# Blocky_Uno_v2.net
KiCad netlist of a schematic drawn in EAGLE
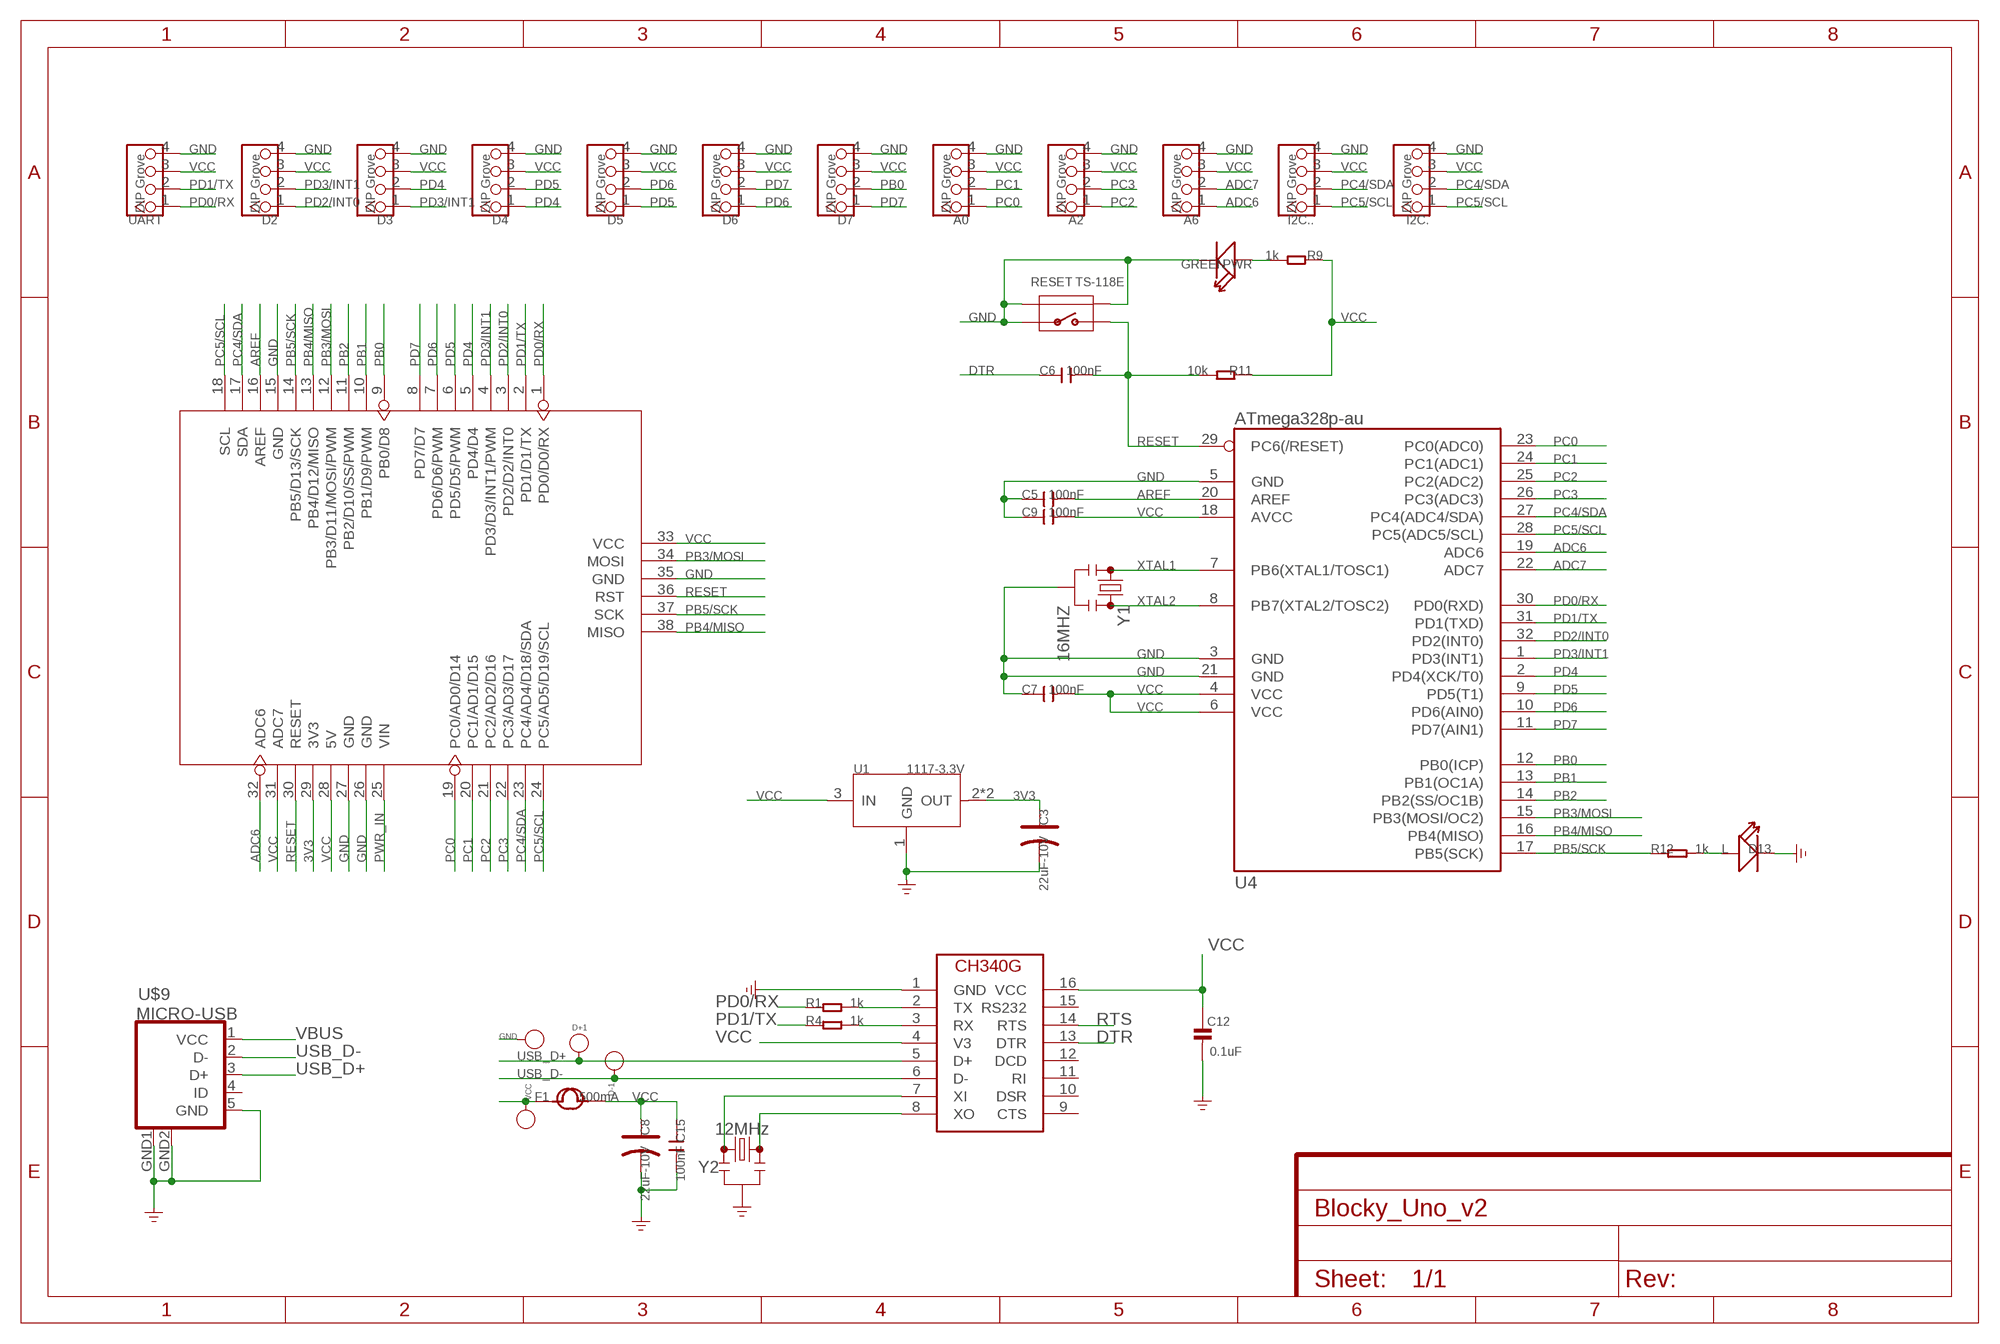
[diagram p0: schematic, sheet 1]

(export (version "E")
  (design (tool "Eeschema 10.0.6"))
  (components
    (comp (ref "A0")
      (value "DIP Grove")
      (footprint "eagle-import:4P-2.0")
      (libsource (lib "eagle-import") (part "Connector _TWIG-4P-2.0-2.0"))
    )
    (comp (ref "A2")
      (value "DIP Grove")
      (footprint "eagle-import:4P-2.0")
      (libsource (lib "eagle-import") (part "Connector _TWIG-4P-2.0-2.0"))
    )
    (comp (ref "A6")
      (value "DIP Grove")
      (footprint "eagle-import:4P-2.0")
      (libsource (lib "eagle-import") (part "Connector _TWIG-4P-2.0-2.0"))
    )
    (comp (ref "C3")
      (value "22uF-10V")
      (footprint "eagle-import:AVX-A")
      (libsource (lib "eagle-import") (part "CAP-AVX-A"))
    )
    (comp (ref "C5")
      (value "100nF")
      (footprint "eagle-import:C0603")
      (libsource (lib "eagle-import") (part "C-0603"))
    )
    (comp (ref "C6")
      (value "100nF")
      (footprint "eagle-import:C0603")
      (libsource (lib "eagle-import") (part "C-0603"))
    )
    (comp (ref "C7")
      (value "100nF")
      (footprint "eagle-import:C0603")
      (libsource (lib "eagle-import") (part "C-0603"))
    )
    (comp (ref "C8")
      (value "22uF-10V")
      (footprint "eagle-import:AVX-A")
      (libsource (lib "eagle-import") (part "CAP-AVX-A"))
    )
    (comp (ref "C9")
      (value "100nF")
      (footprint "eagle-import:C0603")
      (libsource (lib "eagle-import") (part "C-0603"))
    )
    (comp (ref "C12")
      (value "0.1uF")
      (footprint "eagle-import:_0603")
      (libsource (lib "eagle-import") (part "CAP_CERAMIC_0603"))
    )
    (comp (ref "C15")
      (value "100nF")
      (footprint "eagle-import:C0603")
      (libsource (lib "eagle-import") (part "C-0603"))
    )
    (comp (ref "D+1")
      (value "PAD-TEST-POINT'4545'")
      (footprint "eagle-import:TP_4545")
      (fields (field (name "PARTNO") "DNP"))
      (libsource (lib "eagle-import") (part "PAD-TEST-POINT'4545'"))
    )
    (comp (ref "D-1")
      (value "PAD-TEST-POINT'4545'")
      (footprint "eagle-import:TP_4545")
      (fields (field (name "PARTNO") "DNP"))
      (libsource (lib "eagle-import") (part "PAD-TEST-POINT'4545'"))
    )
    (comp (ref "D2")
      (value "DIP Grove")
      (footprint "eagle-import:4P-2.0")
      (libsource (lib "eagle-import") (part "TWIG-4P-2.0-2.0"))
    )
    (comp (ref "D3")
      (value "DIP Grove")
      (footprint "eagle-import:4P-2.0")
      (libsource (lib "eagle-import") (part "TWIG-4P-2.0-2.0"))
    )
    (comp (ref "D4")
      (value "DIP Grove")
      (footprint "eagle-import:4P-2.0")
      (libsource (lib "eagle-import") (part "TWIG-4P-2.0-2.0"))
    )
    (comp (ref "D5")
      (value "DIP Grove")
      (footprint "eagle-import:4P-2.0")
      (libsource (lib "eagle-import") (part "TWIG-4P-2.0-2.0"))
    )
    (comp (ref "D6")
      (value "DIP Grove")
      (footprint "eagle-import:4P-2.0")
      (libsource (lib "eagle-import") (part "TWIG-4P-2.0-2.0"))
    )
    (comp (ref "D7")
      (value "DIP Grove")
      (footprint "eagle-import:4P-2.0")
      (libsource (lib "eagle-import") (part "TWIG-4P-2.0-2.0"))
    )
    (comp (ref "F1")
      (value "500mA")
      (footprint "eagle-import:F1206")
      (libsource (lib "eagle-import") (part "FUSE'1206'"))
    )
    (comp (ref "GND")
      (value "PAD-TEST-POINT'4545'")
      (footprint "eagle-import:TP_4545")
      (fields (field (name "PARTNO") "DNP"))
      (libsource (lib "eagle-import") (part "PAD-TEST-POINT'4545'"))
    )
    (comp (ref "I2C.")
      (value "DIP Grove")
      (footprint "eagle-import:4P-2.0")
      (libsource (lib "eagle-import") (part "TWIG-4P-2.0-2.0"))
    )
    (comp (ref "I2C..")
      (value "DIP Grove")
      (footprint "eagle-import:4P-2.0")
      (libsource (lib "eagle-import") (part "TWIG-4P-2.0-2.0"))
    )
    (comp (ref "L")
      (value "D13")
      (footprint "eagle-import:LED-0603")
      (libsource (lib "eagle-import") (part "LED'0603'"))
    )
    (comp (ref "PWR")
      (value "GREEN")
      (footprint "eagle-import:LED-0603")
      (libsource (lib "eagle-import") (part "LED'0603'"))
    )
    (comp (ref "R1")
      (value "1k")
      (footprint "eagle-import:R0603")
      (libsource (lib "eagle-import") (part "R-0603"))
    )
    (comp (ref "R4")
      (value "1k")
      (footprint "eagle-import:R0603")
      (libsource (lib "eagle-import") (part "R-0603"))
    )
    (comp (ref "R9")
      (value "1k")
      (footprint "eagle-import:R0603")
      (libsource (lib "eagle-import") (part "R-0603"))
    )
    (comp (ref "R11")
      (value "10k")
      (footprint "eagle-import:R0603")
      (libsource (lib "eagle-import") (part "R-0603"))
    )
    (comp (ref "R12")
      (value "1k")
      (footprint "eagle-import:R0603")
      (libsource (lib "eagle-import") (part "R-0603"))
    )
    (comp (ref "RESET")
      (value "TS-118E")
      (footprint "eagle-import:4P-SMD-7X3.5X3.5H")
      (libsource (lib "eagle-import") (part "BUTTON-4P-REINFORCE'TS-1188E'"))
    )
    (comp (ref "U$9")
      (value "MICRO-USB")
      (footprint "eagle-import:MICRO-USB")
      (libsource (lib "eagle-import") (part "MICRO-USB"))
    )
    (comp (ref "U$44")
      (value "CH340G")
      (footprint "eagle-import:SOIC16")
      (libsource (lib "eagle-import") (part "CH340G"))
    )
    (comp (ref "U1")
      (value "1117-3.3V")
      (footprint "eagle-import:SOT89")
      (libsource (lib "eagle-import") (part "LD1117'SOT89'"))
    )
    (comp (ref "U3")
      (value "ARDUINO-38P")
      (footprint "eagle-import:ARDUINO-38P")
      (libsource (lib "eagle-import") (part "ARDUINO-38P"))
    )
    (comp (ref "U4")
      (value "ATmega328p-au")
      (footprint "eagle-import:TQFP32")
      (libsource (lib "eagle-import") (part "ATMEGA8/168/328"))
    )
    (comp (ref "UART")
      (value "DIP Grove")
      (footprint "eagle-import:4P-2.0")
      (libsource (lib "eagle-import") (part "TWIG-4P-2.0-2.0"))
    )
    (comp (ref "VCC")
      (value "PAD-TEST-POINT'4545'")
      (footprint "eagle-import:TP_4545")
      (fields (field (name "PARTNO") "DNP"))
      (libsource (lib "eagle-import") (part "PAD-TEST-POINT'4545'"))
    )
    (comp (ref "Y1")
      (value "16MHZ")
      (footprint "eagle-import:RESONATOR-SMD")
      (libsource (lib "eagle-import") (part "RESONATOR16MHZ"))
    )
    (comp (ref "Y2")
      (value "12MHz")
      (footprint "eagle-import:RESONATOR-SMD-3.2X1.3")
      (libsource (lib "eagle-import") (part "RESONATOR-16MHZSMD_3.2X1.3"))
    )
  )
  (nets
    (net (code "1") (name "/3V3") (class "Default")
      (node (ref "C3") (pin "+") (pinfunction "+_+") (pintype "passive"))
      (node (ref "U1") (pin "2") (pinfunction "OUT_2") (pintype "bidirectional"))
      (node (ref "U1") (pin "4") (pinfunction "OUT_4") (pintype "bidirectional"))
      (node (ref "U3") (pin "29") (pinfunction "3V3_29") (pintype "bidirectional"))
    )
    (net (code "2") (name "/ADC6") (class "Default")
      (node (ref "A6") (pin "1") (pinfunction "1_1") (pintype "bidirectional"))
      (node (ref "U3") (pin "32") (pinfunction "ADC6_32") (pintype "bidirectional"))
      (node (ref "U4") (pin "19") (pinfunction "ADC6_19") (pintype "bidirectional"))
    )
    (net (code "3") (name "/ADC7") (class "Default")
      (node (ref "A6") (pin "2") (pinfunction "2_2") (pintype "bidirectional"))
      (node (ref "U4") (pin "22") (pinfunction "ADC7_22") (pintype "bidirectional"))
    )
    (net (code "4") (name "/AREF") (class "Default")
      (node (ref "C5") (pin "2") (pinfunction "2_2") (pintype "passive"))
      (node (ref "U3") (pin "16") (pinfunction "AREF_16") (pintype "bidirectional"))
      (node (ref "U4") (pin "20") (pinfunction "AREF_20") (pintype "bidirectional"))
    )
    (net (code "5") (name "/DTR") (class "Default")
      (node (ref "C6") (pin "1") (pinfunction "1_1") (pintype "passive"))
      (node (ref "U$44") (pin "13") (pinfunction "DTR_13") (pintype "bidirectional"))
    )
    (net (code "6") (name "/PB0") (class "Default")
      (node (ref "D7") (pin "2") (pinfunction "2_2") (pintype "bidirectional"))
      (node (ref "U3") (pin "9") (pinfunction "PB0/D8_9") (pintype "bidirectional"))
      (node (ref "U4") (pin "12") (pinfunction "PB0(ICP)_12") (pintype "bidirectional"))
    )
    (net (code "7") (name "/PB1") (class "Default")
      (node (ref "U3") (pin "10") (pinfunction "PB1/D9/PWM_10") (pintype "bidirectional"))
      (node (ref "U4") (pin "13") (pinfunction "PB1(OC1A)_13") (pintype "bidirectional"))
    )
    (net (code "8") (name "/PB2") (class "Default")
      (node (ref "U3") (pin "11") (pinfunction "PB2/D10/SS/PWM_11") (pintype "bidirectional"))
      (node (ref "U4") (pin "14") (pinfunction "PB2(SS/OC1B)_14") (pintype "bidirectional"))
    )
    (net (code "9") (name "/PB3{slash}MOSI") (class "Default")
      (node (ref "U3") (pin "12") (pinfunction "PB3/D11/MOSI/PWM_12") (pintype "bidirectional"))
      (node (ref "U3") (pin "34") (pinfunction "MOSI_34") (pintype "bidirectional"))
      (node (ref "U4") (pin "15") (pinfunction "PB3(MOSI/OC2)_15") (pintype "bidirectional"))
    )
    (net (code "10") (name "/PB4{slash}MISO") (class "Default")
      (node (ref "U3") (pin "13") (pinfunction "PB4/D12/MISO_13") (pintype "bidirectional"))
      (node (ref "U3") (pin "38") (pinfunction "MISO_38") (pintype "bidirectional"))
      (node (ref "U4") (pin "16") (pinfunction "PB4(MISO)_16") (pintype "bidirectional"))
    )
    (net (code "11") (name "/PB5{slash}SCK") (class "Default")
      (node (ref "R12") (pin "1") (pinfunction "1_1") (pintype "passive"))
      (node (ref "U3") (pin "14") (pinfunction "PB5/D13/SCK_14") (pintype "bidirectional"))
      (node (ref "U3") (pin "37") (pinfunction "SCK_37") (pintype "bidirectional"))
      (node (ref "U4") (pin "17") (pinfunction "PB5(SCK)_17") (pintype "bidirectional"))
    )
    (net (code "12") (name "/PC0") (class "Default")
      (node (ref "A0") (pin "1") (pinfunction "1_1") (pintype "bidirectional"))
      (node (ref "U3") (pin "19") (pinfunction "PC0/AD0/D14_19") (pintype "bidirectional"))
      (node (ref "U4") (pin "23") (pinfunction "PC0(ADC0)_23") (pintype "bidirectional"))
    )
    (net (code "13") (name "/PC1") (class "Default")
      (node (ref "A0") (pin "2") (pinfunction "2_2") (pintype "bidirectional"))
      (node (ref "U3") (pin "20") (pinfunction "PC1/AD1/D15_20") (pintype "bidirectional"))
      (node (ref "U4") (pin "24") (pinfunction "PC1(ADC1)_24") (pintype "bidirectional"))
    )
    (net (code "14") (name "/PC2") (class "Default")
      (node (ref "A2") (pin "1") (pinfunction "1_1") (pintype "bidirectional"))
      (node (ref "U3") (pin "21") (pinfunction "PC2/AD2/D16_21") (pintype "bidirectional"))
      (node (ref "U4") (pin "25") (pinfunction "PC2(ADC2)_25") (pintype "bidirectional"))
    )
    (net (code "15") (name "/PC3") (class "Default")
      (node (ref "A2") (pin "2") (pinfunction "2_2") (pintype "bidirectional"))
      (node (ref "U3") (pin "22") (pinfunction "PC3/AD3/D17_22") (pintype "bidirectional"))
      (node (ref "U4") (pin "26") (pinfunction "PC3(ADC3)_26") (pintype "bidirectional"))
    )
    (net (code "16") (name "/PC4{slash}SDA") (class "Default")
      (node (ref "I2C.") (pin "2") (pinfunction "2_2") (pintype "bidirectional"))
      (node (ref "I2C..") (pin "2") (pinfunction "2_2") (pintype "bidirectional"))
      (node (ref "U3") (pin "17") (pinfunction "SDA_17") (pintype "bidirectional"))
      (node (ref "U3") (pin "23") (pinfunction "PC4/AD4/D18/SDA_23") (pintype "bidirectional"))
      (node (ref "U4") (pin "27") (pinfunction "PC4(ADC4/SDA)_27") (pintype "bidirectional"))
    )
    (net (code "17") (name "/PC5{slash}SCL") (class "Default")
      (node (ref "I2C.") (pin "1") (pinfunction "1_1") (pintype "bidirectional"))
      (node (ref "I2C..") (pin "1") (pinfunction "1_1") (pintype "bidirectional"))
      (node (ref "U3") (pin "18") (pinfunction "SCL_18") (pintype "bidirectional"))
      (node (ref "U3") (pin "24") (pinfunction "PC5/AD5/D19/SCL_24") (pintype "bidirectional"))
      (node (ref "U4") (pin "28") (pinfunction "PC5(ADC5/SCL)_28") (pintype "bidirectional"))
    )
    (net (code "18") (name "/PD0{slash}RX") (class "Default")
      (node (ref "R1") (pin "1") (pinfunction "1_1") (pintype "passive"))
      (node (ref "U3") (pin "1") (pinfunction "PD0/D0/RX_1") (pintype "bidirectional"))
      (node (ref "U4") (pin "30") (pinfunction "PD0(RXD)_30") (pintype "bidirectional"))
      (node (ref "UART") (pin "1") (pinfunction "1_1") (pintype "bidirectional"))
    )
    (net (code "19") (name "/PD1{slash}TX") (class "Default")
      (node (ref "R4") (pin "1") (pinfunction "1_1") (pintype "passive"))
      (node (ref "U3") (pin "2") (pinfunction "PD1/D1/TX_2") (pintype "bidirectional"))
      (node (ref "U4") (pin "31") (pinfunction "PD1(TXD)_31") (pintype "bidirectional"))
      (node (ref "UART") (pin "2") (pinfunction "2_2") (pintype "bidirectional"))
    )
    (net (code "20") (name "/PD2{slash}INT0") (class "Default")
      (node (ref "D2") (pin "1") (pinfunction "1_1") (pintype "bidirectional"))
      (node (ref "U3") (pin "3") (pinfunction "PD2/D2/INT0_3") (pintype "bidirectional"))
      (node (ref "U4") (pin "32") (pinfunction "PD2(INT0)_32") (pintype "bidirectional"))
    )
    (net (code "21") (name "/PD3{slash}INT1") (class "Default")
      (node (ref "D2") (pin "2") (pinfunction "2_2") (pintype "bidirectional"))
      (node (ref "D3") (pin "1") (pinfunction "1_1") (pintype "bidirectional"))
      (node (ref "U3") (pin "4") (pinfunction "PD3/D3/INT1/PWM_4") (pintype "bidirectional"))
      (node (ref "U4") (pin "1") (pinfunction "PD3(INT1)_1") (pintype "bidirectional"))
    )
    (net (code "22") (name "/PD4") (class "Default")
      (node (ref "D3") (pin "2") (pinfunction "2_2") (pintype "bidirectional"))
      (node (ref "D4") (pin "1") (pinfunction "1_1") (pintype "bidirectional"))
      (node (ref "U3") (pin "5") (pinfunction "PD4/D4_5") (pintype "bidirectional"))
      (node (ref "U4") (pin "2") (pinfunction "PD4(XCK/T0)_2") (pintype "bidirectional"))
    )
    (net (code "23") (name "/PD5") (class "Default")
      (node (ref "D4") (pin "2") (pinfunction "2_2") (pintype "bidirectional"))
      (node (ref "D5") (pin "1") (pinfunction "1_1") (pintype "bidirectional"))
      (node (ref "U3") (pin "6") (pinfunction "PD5/D5/PWM_6") (pintype "bidirectional"))
      (node (ref "U4") (pin "9") (pinfunction "PD5(T1)_9") (pintype "bidirectional"))
    )
    (net (code "24") (name "/PD6") (class "Default")
      (node (ref "D5") (pin "2") (pinfunction "2_2") (pintype "bidirectional"))
      (node (ref "D6") (pin "1") (pinfunction "1_1") (pintype "bidirectional"))
      (node (ref "U3") (pin "7") (pinfunction "PD6/D6/PWM_7") (pintype "bidirectional"))
      (node (ref "U4") (pin "10") (pinfunction "PD6(AIN0)_10") (pintype "bidirectional"))
    )
    (net (code "25") (name "/PD7") (class "Default")
      (node (ref "D6") (pin "2") (pinfunction "2_2") (pintype "bidirectional"))
      (node (ref "D7") (pin "1") (pinfunction "1_1") (pintype "bidirectional"))
      (node (ref "U3") (pin "8") (pinfunction "PD7/D7_8") (pintype "bidirectional"))
      (node (ref "U4") (pin "11") (pinfunction "PD7(AIN1)_11") (pintype "bidirectional"))
    )
    (net (code "26") (name "/PWR_IN") (class "Default")
      (node (ref "U3") (pin "25") (pinfunction "VIN_25") (pintype "bidirectional"))
    )
    (net (code "27") (name "/RESET") (class "Default")
      (node (ref "C6") (pin "2") (pinfunction "2_2") (pintype "passive"))
      (node (ref "R11") (pin "2") (pinfunction "2_2") (pintype "passive"))
      (node (ref "RESET") (pin "2") (pinfunction "2_2") (pintype "bidirectional"))
      (node (ref "U3") (pin "30") (pinfunction "RESET_30") (pintype "bidirectional"))
      (node (ref "U3") (pin "36") (pinfunction "RST_36") (pintype "bidirectional"))
      (node (ref "U4") (pin "29") (pinfunction "PC6(/RESET)_29") (pintype "bidirectional"))
    )
    (net (code "28") (name "/RTS") (class "Default")
      (node (ref "U$44") (pin "14") (pinfunction "RTS_14") (pintype "bidirectional"))
    )
    (net (code "29") (name "/USB_D+") (class "Default")
      (node (ref "D+1") (pin "T") (pinfunction "T_T") (pintype "bidirectional"))
      (node (ref "U$44") (pin "5") (pinfunction "D+_5") (pintype "bidirectional"))
      (node (ref "U$9") (pin "3") (pinfunction "D+_3") (pintype "bidirectional"))
    )
    (net (code "30") (name "/USB_D-") (class "Default")
      (node (ref "D-1") (pin "T") (pinfunction "T_T") (pintype "bidirectional"))
      (node (ref "U$44") (pin "6") (pinfunction "D-_6") (pintype "bidirectional"))
      (node (ref "U$9") (pin "2") (pinfunction "D-_2") (pintype "bidirectional"))
    )
    (net (code "31") (name "/VBUS") (class "Default")
      (node (ref "F1") (pin "1") (pinfunction "1_1") (pintype "bidirectional"))
      (node (ref "U$9") (pin "1") (pinfunction "VCC_1") (pintype "power_in"))
      (node (ref "VCC") (pin "T") (pinfunction "T_T") (pintype "bidirectional"))
    )
    (net (code "32") (name "/VCC") (class "Default")
      (node (ref "A0") (pin "3") (pinfunction "3_3") (pintype "bidirectional"))
      (node (ref "A2") (pin "3") (pinfunction "3_3") (pintype "bidirectional"))
      (node (ref "A6") (pin "3") (pinfunction "3_3") (pintype "bidirectional"))
      (node (ref "C12") (pin "1") (pinfunction "P$1_1") (pintype "passive"))
      (node (ref "C15") (pin "1") (pinfunction "1_1") (pintype "passive"))
      (node (ref "C7") (pin "2") (pinfunction "2_2") (pintype "passive"))
      (node (ref "C8") (pin "+") (pinfunction "+_+") (pintype "passive"))
      (node (ref "C9") (pin "2") (pinfunction "2_2") (pintype "passive"))
      (node (ref "D2") (pin "3") (pinfunction "3_3") (pintype "bidirectional"))
      (node (ref "D3") (pin "3") (pinfunction "3_3") (pintype "bidirectional"))
      (node (ref "D4") (pin "3") (pinfunction "3_3") (pintype "bidirectional"))
      (node (ref "D5") (pin "3") (pinfunction "3_3") (pintype "bidirectional"))
      (node (ref "D6") (pin "3") (pinfunction "3_3") (pintype "bidirectional"))
      (node (ref "D7") (pin "3") (pinfunction "3_3") (pintype "bidirectional"))
      (node (ref "F1") (pin "2") (pinfunction "2_2") (pintype "bidirectional"))
      (node (ref "I2C.") (pin "3") (pinfunction "3_3") (pintype "bidirectional"))
      (node (ref "I2C..") (pin "3") (pinfunction "3_3") (pintype "bidirectional"))
      (node (ref "R11") (pin "1") (pinfunction "1_1") (pintype "passive"))
      (node (ref "R9") (pin "1") (pinfunction "1_1") (pintype "passive"))
      (node (ref "U$44") (pin "16") (pinfunction "VCC_16") (pintype "bidirectional"))
      (node (ref "U$44") (pin "4") (pinfunction "V3_4") (pintype "bidirectional"))
      (node (ref "U1") (pin "3") (pinfunction "IN_3") (pintype "bidirectional"))
      (node (ref "U3") (pin "28") (pinfunction "5V_28") (pintype "bidirectional"))
      (node (ref "U3") (pin "31") (pinfunction "ADC7_31") (pintype "bidirectional"))
      (node (ref "U3") (pin "33") (pinfunction "VCC_33") (pintype "bidirectional"))
      (node (ref "U4") (pin "18") (pinfunction "AVCC_18") (pintype "bidirectional"))
      (node (ref "U4") (pin "4") (pinfunction "VCC_4") (pintype "bidirectional"))
      (node (ref "U4") (pin "6") (pinfunction "VCC_6") (pintype "bidirectional"))
      (node (ref "UART") (pin "3") (pinfunction "3_3") (pintype "bidirectional"))
    )
    (net (code "33") (name "/XTAL1") (class "Default")
      (node (ref "U4") (pin "7") (pinfunction "PB6(XTAL1/TOSC1)_7") (pintype "bidirectional"))
      (node (ref "Y1") (pin "1") (pinfunction "1_1") (pintype "passive"))
    )
    (net (code "34") (name "/XTAL2") (class "Default")
      (node (ref "U4") (pin "8") (pinfunction "PB7(XTAL2/TOSC2)_8") (pintype "bidirectional"))
      (node (ref "Y1") (pin "3") (pinfunction "3_3") (pintype "passive"))
    )
    (net (code "35") (name "GND_POWER") (class "Default")
      (node (ref "A0") (pin "4") (pinfunction "4_4") (pintype "bidirectional"))
      (node (ref "A2") (pin "4") (pinfunction "4_4") (pintype "bidirectional"))
      (node (ref "A6") (pin "4") (pinfunction "4_4") (pintype "bidirectional"))
      (node (ref "C12") (pin "2") (pinfunction "P$2_2") (pintype "passive"))
      (node (ref "C15") (pin "2") (pinfunction "2_2") (pintype "passive"))
      (node (ref "C3") (pin "-") (pinfunction "-_-") (pintype "passive"))
      (node (ref "C5") (pin "1") (pinfunction "1_1") (pintype "passive"))
      (node (ref "C7") (pin "1") (pinfunction "1_1") (pintype "passive"))
      (node (ref "C8") (pin "-") (pinfunction "-_-") (pintype "passive"))
      (node (ref "C9") (pin "1") (pinfunction "1_1") (pintype "passive"))
      (node (ref "D2") (pin "4") (pinfunction "4_4") (pintype "bidirectional"))
      (node (ref "D3") (pin "4") (pinfunction "4_4") (pintype "bidirectional"))
      (node (ref "D4") (pin "4") (pinfunction "4_4") (pintype "bidirectional"))
      (node (ref "D5") (pin "4") (pinfunction "4_4") (pintype "bidirectional"))
      (node (ref "D6") (pin "4") (pinfunction "4_4") (pintype "bidirectional"))
      (node (ref "D7") (pin "4") (pinfunction "4_4") (pintype "bidirectional"))
      (node (ref "GND") (pin "T") (pinfunction "T_T") (pintype "bidirectional"))
      (node (ref "I2C.") (pin "4") (pinfunction "4_4") (pintype "bidirectional"))
      (node (ref "I2C..") (pin "4") (pinfunction "4_4") (pintype "bidirectional"))
      (node (ref "L") (pin "-") (pinfunction "-_-") (pintype "passive"))
      (node (ref "PWR") (pin "-") (pinfunction "-_-") (pintype "passive"))
      (node (ref "RESET") (pin "1") (pinfunction "1_1") (pintype "bidirectional"))
      (node (ref "RESET") (pin "S1") (pinfunction "S1_S1") (pintype "bidirectional"))
      (node (ref "RESET") (pin "S2") (pinfunction "S2_S2") (pintype "bidirectional"))
      (node (ref "U$44") (pin "1") (pinfunction "GND_1") (pintype "bidirectional"))
      (node (ref "U$9") (pin "5") (pinfunction "GND_5") (pintype "power_in"))
      (node (ref "U$9") (pin "GND1") (pinfunction "GND_GND1") (pintype "power_in"))
      (node (ref "U$9") (pin "GND2") (pinfunction "GND_GND2") (pintype "power_in"))
      (node (ref "U1") (pin "1") (pinfunction "GND_1") (pintype "bidirectional"))
      (node (ref "U3") (pin "15") (pinfunction "GND_15") (pintype "bidirectional"))
      (node (ref "U3") (pin "26") (pinfunction "GND_26") (pintype "bidirectional"))
      (node (ref "U3") (pin "27") (pinfunction "GND_27") (pintype "bidirectional"))
      (node (ref "U3") (pin "35") (pinfunction "GND_35") (pintype "bidirectional"))
      (node (ref "U4") (pin "21") (pinfunction "GND_21") (pintype "bidirectional"))
      (node (ref "U4") (pin "3") (pinfunction "GND_3") (pintype "bidirectional"))
      (node (ref "U4") (pin "5") (pinfunction "GND_5") (pintype "bidirectional"))
      (node (ref "UART") (pin "4") (pinfunction "4_4") (pintype "bidirectional"))
      (node (ref "Y1") (pin "2") (pinfunction "2_2") (pintype "passive"))
      (node (ref "Y2") (pin "2") (pinfunction "2_2") (pintype "passive"))
    )
    (net (code "36") (name "Net-(L-Pad+)") (class "Default")
      (node (ref "L") (pin "+") (pinfunction "+_+") (pintype "passive"))
      (node (ref "R12") (pin "2") (pinfunction "2_2") (pintype "passive"))
    )
    (net (code "37") (name "Net-(PWR-Pad+)") (class "Default")
      (node (ref "PWR") (pin "+") (pinfunction "+_+") (pintype "passive"))
      (node (ref "R9") (pin "2") (pinfunction "2_2") (pintype "passive"))
    )
    (net (code "38") (name "Net-(U$44-RX)") (class "Default")
      (node (ref "R4") (pin "2") (pinfunction "2_2") (pintype "passive"))
      (node (ref "U$44") (pin "3") (pinfunction "RX_3") (pintype "bidirectional"))
    )
    (net (code "39") (name "Net-(U$44-TX)") (class "Default")
      (node (ref "R1") (pin "2") (pinfunction "2_2") (pintype "passive"))
      (node (ref "U$44") (pin "2") (pinfunction "TX_2") (pintype "bidirectional"))
    )
    (net (code "40") (name "Net-(U$44-XI)") (class "Default")
      (node (ref "U$44") (pin "7") (pinfunction "XI_7") (pintype "bidirectional"))
      (node (ref "Y2") (pin "1") (pinfunction "1_1") (pintype "passive"))
    )
    (net (code "41") (name "Net-(U$44-XO)") (class "Default")
      (node (ref "U$44") (pin "8") (pinfunction "XO_8") (pintype "bidirectional"))
      (node (ref "Y2") (pin "3") (pinfunction "3_3") (pintype "passive"))
    )
    (net (code "42") (name "unconnected-(U$9-ID-Pad4)") (class "Default")
      (node (ref "U$9") (pin "4") (pinfunction "ID_4") (pintype "bidirectional"))
    )
    (net (code "43") (name "unconnected-(U$44-CTS-Pad9)") (class "Default")
      (node (ref "U$44") (pin "9") (pinfunction "CTS_9") (pintype "bidirectional"))
    )
    (net (code "44") (name "unconnected-(U$44-DCD-Pad12)") (class "Default")
      (node (ref "U$44") (pin "12") (pinfunction "DCD_12") (pintype "bidirectional"))
    )
    (net (code "45") (name "unconnected-(U$44-DSR-Pad10)") (class "Default")
      (node (ref "U$44") (pin "10") (pinfunction "DSR_10") (pintype "bidirectional"))
    )
    (net (code "46") (name "unconnected-(U$44-RI-Pad11)") (class "Default")
      (node (ref "U$44") (pin "11") (pinfunction "RI_11") (pintype "bidirectional"))
    )
    (net (code "47") (name "unconnected-(U$44-RS232-Pad15)") (class "Default")
      (node (ref "U$44") (pin "15") (pinfunction "RS232_15") (pintype "bidirectional"))
    )
  )
)
